# ControlV2.net
KiCad netlist of a schematic drawn in EAGLE
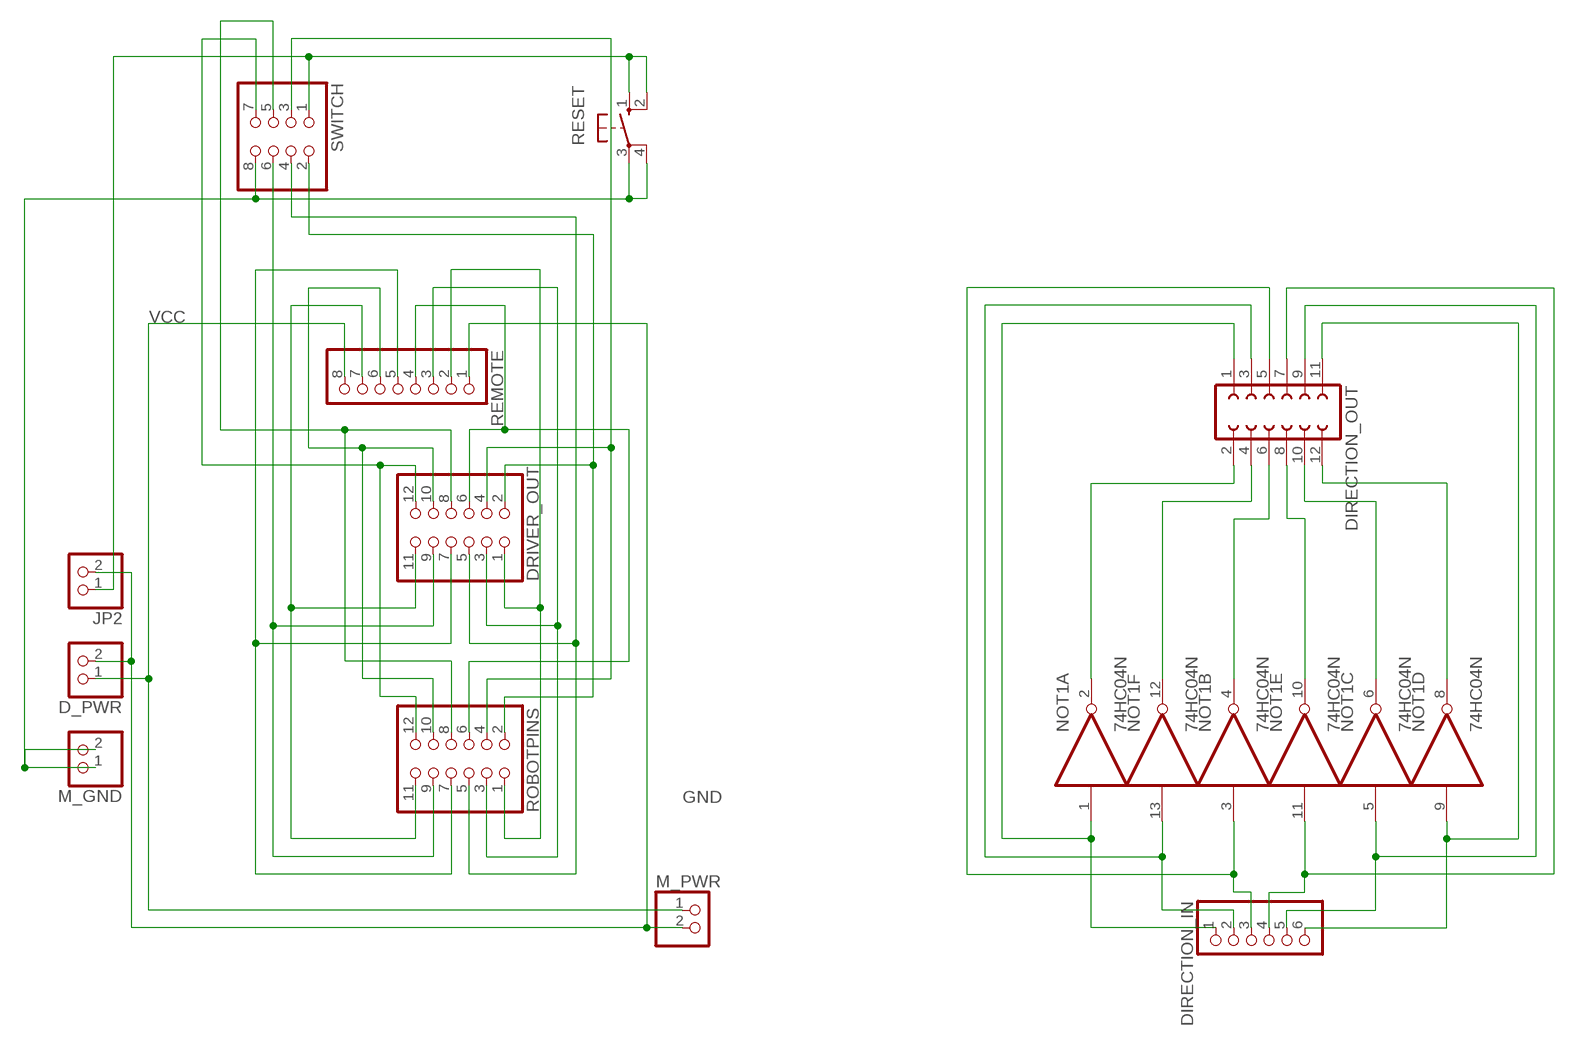
[diagram p0: schematic, sheet 1]

(export (version "E")
  (design (tool "Eeschema 10.0.6"))
  (components
    (comp (ref "DIRECTION_IN")
      (value "PINHD-1X6")
      (footprint "eagle-import:1X06")
      (libsource (lib "eagle-import") (part "PINHD-1X6"))
    )
    (comp (ref "DIRECTION_OUT")
      (value "FE06-2")
      (footprint "eagle-import:FE06-2")
      (libsource (lib "eagle-import") (part "FE06-2"))
    )
    (comp (ref "DRIVER_OUT")
      (value "PINHD-2X6")
      (footprint "eagle-import:2X06")
      (libsource (lib "eagle-import") (part "PINHD-2X6"))
    )
    (comp (ref "D_PWR")
      (value "PINHD-1X2")
      (footprint "eagle-import:1X02")
      (libsource (lib "eagle-import") (part "PINHD-1X2"))
    )
    (comp (ref "JP2")
      (value "PINHD-1X2")
      (footprint "eagle-import:1X02")
      (libsource (lib "eagle-import") (part "PINHD-1X2"))
    )
    (comp (ref "M_GND")
      (value "PINHD-1X2")
      (footprint "eagle-import:1X02")
      (libsource (lib "eagle-import") (part "PINHD-1X2"))
    )
    (comp (ref "M_PWR")
      (value "PINHD-1X2")
      (footprint "eagle-import:1X02")
      (libsource (lib "eagle-import") (part "PINHD-1X2"))
    )
    (comp (ref "NOT1")
      (value "74HC04N")
      (footprint "eagle-import:DIL14")
      (fields (field (name "SPICEPREFIX") "B"))
      (libsource (lib "eagle-import") (part "7404NHC"))
    )
    (comp (ref "REMOTE")
      (value "PINHD-1X8")
      (footprint "eagle-import:1X08")
      (libsource (lib "eagle-import") (part "PINHD-1X8"))
    )
    (comp (ref "RESET")
      (value "10-XX")
      (footprint "eagle-import:B3F-10XX")
      (fields (field (name "MPN") "B3F-1000"))
      (libsource (lib "eagle-import") (part "10-XX"))
    )
    (comp (ref "ROBOTPINS")
      (value "PINHD-2X6")
      (footprint "eagle-import:2X06")
      (libsource (lib "eagle-import") (part "PINHD-2X6"))
    )
    (comp (ref "SWITCH")
      (value "PINHD-2X4")
      (footprint "eagle-import:2X04")
      (fields (field (name "SPICEPREFIX") "X"))
      (libsource (lib "eagle-import") (part "PINHD-2X4"))
    )
  )
  (nets
    (net (code "1") (name "/GND") (class "Default")
      (node (ref "D_PWR") (pin "2") (pinfunction "2_2") (pintype "passive"))
      (node (ref "JP2") (pin "2") (pinfunction "2_2") (pintype "passive"))
      (node (ref "M_PWR") (pin "2") (pinfunction "2_2") (pintype "passive"))
      (node (ref "REMOTE") (pin "1") (pinfunction "1_1") (pintype "passive"))
    )
    (net (code "2") (name "/VCC") (class "Default")
      (node (ref "D_PWR") (pin "1") (pinfunction "1_1") (pintype "passive"))
      (node (ref "M_PWR") (pin "1") (pinfunction "1_1") (pintype "passive"))
      (node (ref "REMOTE") (pin "8") (pinfunction "8_8") (pintype "passive"))
    )
    (net (code "3") (name "Net-(DRIVER_OUT-Pad1)") (class "Default")
      (node (ref "DRIVER_OUT") (pin "1") (pinfunction "1_1") (pintype "passive"))
      (node (ref "REMOTE") (pin "2") (pinfunction "2_2") (pintype "passive"))
      (node (ref "ROBOTPINS") (pin "1") (pinfunction "1_1") (pintype "passive"))
    )
    (net (code "4") (name "Net-(DRIVER_OUT-Pad2)") (class "Default")
      (node (ref "DRIVER_OUT") (pin "2") (pinfunction "2_2") (pintype "passive"))
      (node (ref "ROBOTPINS") (pin "2") (pinfunction "2_2") (pintype "passive"))
      (node (ref "SWITCH") (pin "2") (pinfunction "2_2") (pintype "passive"))
    )
    (net (code "5") (name "Net-(DRIVER_OUT-Pad3)") (class "Default")
      (node (ref "DRIVER_OUT") (pin "3") (pinfunction "3_3") (pintype "passive"))
      (node (ref "REMOTE") (pin "3") (pinfunction "3_3") (pintype "passive"))
      (node (ref "ROBOTPINS") (pin "3") (pinfunction "3_3") (pintype "passive"))
    )
    (net (code "6") (name "Net-(DRIVER_OUT-Pad4)") (class "Default")
      (node (ref "DRIVER_OUT") (pin "4") (pinfunction "4_4") (pintype "passive"))
      (node (ref "ROBOTPINS") (pin "4") (pinfunction "4_4") (pintype "passive"))
      (node (ref "SWITCH") (pin "3") (pinfunction "3_3") (pintype "passive"))
    )
    (net (code "7") (name "Net-(DRIVER_OUT-Pad5)") (class "Default")
      (node (ref "DRIVER_OUT") (pin "5") (pinfunction "5_5") (pintype "passive"))
      (node (ref "ROBOTPINS") (pin "5") (pinfunction "5_5") (pintype "passive"))
      (node (ref "SWITCH") (pin "4") (pinfunction "4_4") (pintype "passive"))
    )
    (net (code "8") (name "Net-(DRIVER_OUT-Pad6)") (class "Default")
      (node (ref "DRIVER_OUT") (pin "6") (pinfunction "6_6") (pintype "passive"))
      (node (ref "REMOTE") (pin "4") (pinfunction "4_4") (pintype "passive"))
      (node (ref "ROBOTPINS") (pin "6") (pinfunction "6_6") (pintype "passive"))
    )
    (net (code "9") (name "Net-(DRIVER_OUT-Pad7)") (class "Default")
      (node (ref "DRIVER_OUT") (pin "7") (pinfunction "7_7") (pintype "passive"))
      (node (ref "REMOTE") (pin "5") (pinfunction "5_5") (pintype "passive"))
      (node (ref "ROBOTPINS") (pin "7") (pinfunction "7_7") (pintype "passive"))
    )
    (net (code "10") (name "Net-(DRIVER_OUT-Pad8)") (class "Default")
      (node (ref "DRIVER_OUT") (pin "8") (pinfunction "8_8") (pintype "passive"))
      (node (ref "ROBOTPINS") (pin "8") (pinfunction "8_8") (pintype "passive"))
      (node (ref "SWITCH") (pin "5") (pinfunction "5_5") (pintype "passive"))
    )
    (net (code "11") (name "Net-(DRIVER_OUT-Pad9)") (class "Default")
      (node (ref "DRIVER_OUT") (pin "9") (pinfunction "9_9") (pintype "passive"))
      (node (ref "ROBOTPINS") (pin "9") (pinfunction "9_9") (pintype "passive"))
      (node (ref "SWITCH") (pin "6") (pinfunction "6_6") (pintype "passive"))
    )
    (net (code "12") (name "Net-(DRIVER_OUT-Pad10)") (class "Default")
      (node (ref "DRIVER_OUT") (pin "10") (pinfunction "10_10") (pintype "passive"))
      (node (ref "REMOTE") (pin "6") (pinfunction "6_6") (pintype "passive"))
      (node (ref "ROBOTPINS") (pin "10") (pinfunction "10_10") (pintype "passive"))
    )
    (net (code "13") (name "Net-(DRIVER_OUT-Pad11)") (class "Default")
      (node (ref "DRIVER_OUT") (pin "11") (pinfunction "11_11") (pintype "passive"))
      (node (ref "REMOTE") (pin "7") (pinfunction "7_7") (pintype "passive"))
      (node (ref "ROBOTPINS") (pin "11") (pinfunction "11_11") (pintype "passive"))
    )
    (net (code "14") (name "Net-(DRIVER_OUT-Pad12)") (class "Default")
      (node (ref "DRIVER_OUT") (pin "12") (pinfunction "12_12") (pintype "passive"))
      (node (ref "ROBOTPINS") (pin "12") (pinfunction "12_12") (pintype "passive"))
      (node (ref "SWITCH") (pin "7") (pinfunction "7_7") (pintype "passive"))
    )
    (net (code "15") (name "Net-(NOT1A-I)") (class "Default")
      (node (ref "DIRECTION_IN") (pin "1") (pinfunction "1_1") (pintype "passive"))
      (node (ref "DIRECTION_OUT") (pin "1") (pinfunction "1_1") (pintype "passive"))
      (node (ref "NOT1") (pin "1") (pinfunction "I_1") (pintype "input"))
    )
    (net (code "16") (name "Net-(NOT1A-O)") (class "Default")
      (node (ref "DIRECTION_OUT") (pin "2") (pinfunction "2_2") (pintype "passive"))
      (node (ref "NOT1") (pin "2") (pinfunction "O_2") (pintype "output"))
    )
    (net (code "17") (name "Net-(NOT1B-I)") (class "Default")
      (node (ref "DIRECTION_IN") (pin "3") (pinfunction "3_3") (pintype "passive"))
      (node (ref "DIRECTION_OUT") (pin "5") (pinfunction "5_5") (pintype "passive"))
      (node (ref "NOT1") (pin "3") (pinfunction "I_3") (pintype "input"))
    )
    (net (code "18") (name "Net-(NOT1B-O)") (class "Default")
      (node (ref "DIRECTION_OUT") (pin "6") (pinfunction "6_6") (pintype "passive"))
      (node (ref "NOT1") (pin "4") (pinfunction "O_4") (pintype "output"))
    )
    (net (code "19") (name "Net-(NOT1C-I)") (class "Default")
      (node (ref "DIRECTION_IN") (pin "5") (pinfunction "5_5") (pintype "passive"))
      (node (ref "DIRECTION_OUT") (pin "9") (pinfunction "9_9") (pintype "passive"))
      (node (ref "NOT1") (pin "5") (pinfunction "I_5") (pintype "input"))
    )
    (net (code "20") (name "Net-(NOT1C-O)") (class "Default")
      (node (ref "DIRECTION_OUT") (pin "10") (pinfunction "10_10") (pintype "passive"))
      (node (ref "NOT1") (pin "6") (pinfunction "O_6") (pintype "output"))
    )
    (net (code "21") (name "Net-(NOT1D-I)") (class "Default")
      (node (ref "DIRECTION_IN") (pin "6") (pinfunction "6_6") (pintype "passive"))
      (node (ref "DIRECTION_OUT") (pin "11") (pinfunction "11_11") (pintype "passive"))
      (node (ref "NOT1") (pin "9") (pinfunction "I_9") (pintype "input"))
    )
    (net (code "22") (name "Net-(NOT1D-O)") (class "Default")
      (node (ref "DIRECTION_OUT") (pin "12") (pinfunction "12_12") (pintype "passive"))
      (node (ref "NOT1") (pin "8") (pinfunction "O_8") (pintype "output"))
    )
    (net (code "23") (name "Net-(NOT1E-I)") (class "Default")
      (node (ref "DIRECTION_IN") (pin "4") (pinfunction "4_4") (pintype "passive"))
      (node (ref "DIRECTION_OUT") (pin "7") (pinfunction "7_7") (pintype "passive"))
      (node (ref "NOT1") (pin "11") (pinfunction "I_11") (pintype "input"))
    )
    (net (code "24") (name "Net-(NOT1E-O)") (class "Default")
      (node (ref "DIRECTION_OUT") (pin "8") (pinfunction "8_8") (pintype "passive"))
      (node (ref "NOT1") (pin "10") (pinfunction "O_10") (pintype "output"))
    )
    (net (code "25") (name "Net-(NOT1F-I)") (class "Default")
      (node (ref "DIRECTION_IN") (pin "2") (pinfunction "2_2") (pintype "passive"))
      (node (ref "DIRECTION_OUT") (pin "3") (pinfunction "3_3") (pintype "passive"))
      (node (ref "NOT1") (pin "13") (pinfunction "I_13") (pintype "input"))
    )
    (net (code "26") (name "Net-(NOT1F-O)") (class "Default")
      (node (ref "DIRECTION_OUT") (pin "4") (pinfunction "4_4") (pintype "passive"))
      (node (ref "NOT1") (pin "12") (pinfunction "O_12") (pintype "output"))
    )
    (net (code "27") (name "Net-(RESET-P)") (class "Default")
      (node (ref "M_GND") (pin "1") (pinfunction "1_1") (pintype "passive"))
      (node (ref "M_GND") (pin "2") (pinfunction "2_2") (pintype "passive"))
      (node (ref "RESET") (pin "3") (pinfunction "P_3") (pintype "passive"))
      (node (ref "RESET") (pin "4") (pinfunction "P1_4") (pintype "passive"))
      (node (ref "SWITCH") (pin "8") (pinfunction "8_8") (pintype "passive"))
    )
    (net (code "28") (name "Net-(RESET-S)") (class "Default")
      (node (ref "JP2") (pin "1") (pinfunction "1_1") (pintype "passive"))
      (node (ref "RESET") (pin "1") (pinfunction "S_1") (pintype "passive"))
      (node (ref "RESET") (pin "2") (pinfunction "S1_2") (pintype "passive"))
      (node (ref "SWITCH") (pin "1") (pinfunction "1_1") (pintype "passive"))
    )
  )
)
